# MPU6050.net
KiCad netlist of a schematic drawn in Altium Designer
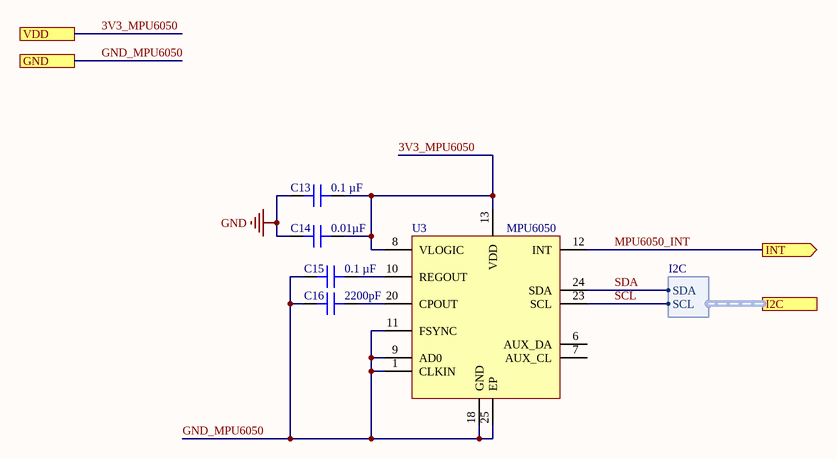
[diagram p0: MPU6050.SchDoc]

(export (version "E")
  (design (tool "Eeschema 10.0.6"))
  (components
    (comp (ref "C13")
      (value "0.1 µF")
      (footprint "CAP 0402_1005")
      (description "CAP CER 0.1UF 16V X7R 0402")
      (fields (field (name "PART NUMBER") "C0402C104K4RACAUTO") (field (name "MANUFACTURER") "KEMET"))
      (libsource (lib "Celestial Altium Library - altium_library") (part "Capacitor"))
    )
    (comp (ref "C14")
      (value "0.01µF")
      (footprint "CAP 0603_1608")
      (description "CAP CER 0.01UF 250V X7R 0603")
      (fields (field (name "PART NUMBER") "C0603C103KARACAUTO") (field (name "MANUFACTURER") "KEMET"))
      (libsource (lib "Celestial Altium Library - altium_library") (part "Capacitor"))
    )
    (comp (ref "C15")
      (value "0.1 µF")
      (footprint "CAP 0402_1005")
      (description "CAP CER 0.1UF 16V X7R 0402")
      (fields (field (name "PART NUMBER") "C0402C104K4RACAUTO") (field (name "MANUFACTURER") "KEMET"))
      (libsource (lib "Celestial Altium Library - altium_library") (part "Capacitor"))
    )
    (comp (ref "C16")
      (value "2200pF")
      (footprint "CAP 0603_1608")
      (description "CAP CER 2200PF 50V 0603 EPOXY")
      (fields
        (field (name "PART NUMBER") "CGA3E2X8R1H222M080AD")
        (field (name "MANUFACTURER") "TDK Corporation")
      )
      (libsource (lib "Celestial Altium Library - altium_library") (part "Capacitor"))
    )
    (comp (ref "U3") (value "MPU6050") (footprint "IC_MPU6050") (libsource (lib "IC") (part "MPU6050")))
  )
  (nets
    (net (code "2") (name "/3V3_MPU6050") (class "Default")
      (node (ref "C13") (pin "1") (pinfunction "1_1") (pintype "passive"))
      (node (ref "C14") (pin "2") (pinfunction "2_2") (pintype "passive"))
      (node (ref "U3") (pin "13") (pinfunction "VDD_13") (pintype "passive"))
      (node (ref "U3") (pin "8") (pinfunction "VLOGIC_8") (pintype "passive"))
    )
    (net (code "3") (name "/MPU6050_INT") (class "Default")
      (node (ref "U3") (pin "12") (pinfunction "INT_12") (pintype "passive"))
    )
    (net (code "4") (name "/SCL") (class "Default")
      (node (ref "U3") (pin "23") (pinfunction "SCL_23") (pintype "passive"))
    )
    (net (code "5") (name "/SDA") (class "Default")
      (node (ref "U3") (pin "24") (pinfunction "SDA_24") (pintype "passive"))
    )
    (net (code "7") (name "GND") (class "Default")
      (node (ref "C13") (pin "2") (pinfunction "2_2") (pintype "passive"))
      (node (ref "C14") (pin "1") (pinfunction "1_1") (pintype "passive"))
      (node (ref "C15") (pin "2") (pinfunction "2_2") (pintype "passive"))
      (node (ref "C16") (pin "2") (pinfunction "2_2") (pintype "passive"))
      (node (ref "U3") (pin "1") (pinfunction "CLKIN_1") (pintype "passive"))
      (node (ref "U3") (pin "11") (pinfunction "FSYNC_11") (pintype "passive"))
      (node (ref "U3") (pin "18") (pinfunction "GND_18") (pintype "passive"))
      (node (ref "U3") (pin "25") (pinfunction "EP_25") (pintype "passive"))
      (node (ref "U3") (pin "9") (pinfunction "AD0_9") (pintype "passive"))
    )
    (net (code "8") (name "Net-(U3-CPOUT)") (class "Default")
      (node (ref "C16") (pin "1") (pinfunction "1_1") (pintype "passive"))
      (node (ref "U3") (pin "20") (pinfunction "CPOUT_20") (pintype "passive"))
    )
    (net (code "9") (name "Net-(U3-REGOUT)") (class "Default")
      (node (ref "C15") (pin "1") (pinfunction "1_1") (pintype "passive"))
      (node (ref "U3") (pin "10") (pinfunction "REGOUT_10") (pintype "passive"))
    )
    (net (code "10") (name "unconnected-(U3-AUX_CL-Pad7)") (class "Default")
      (node (ref "U3") (pin "7") (pinfunction "AUX_CL_7") (pintype "passive"))
    )
    (net (code "11") (name "unconnected-(U3-AUX_DA-Pad6)") (class "Default")
      (node (ref "U3") (pin "6") (pinfunction "AUX_DA_6") (pintype "passive"))
    )
  )
)
